# uBus-V1_0.net
KiCad netlist of a schematic drawn in EAGLE
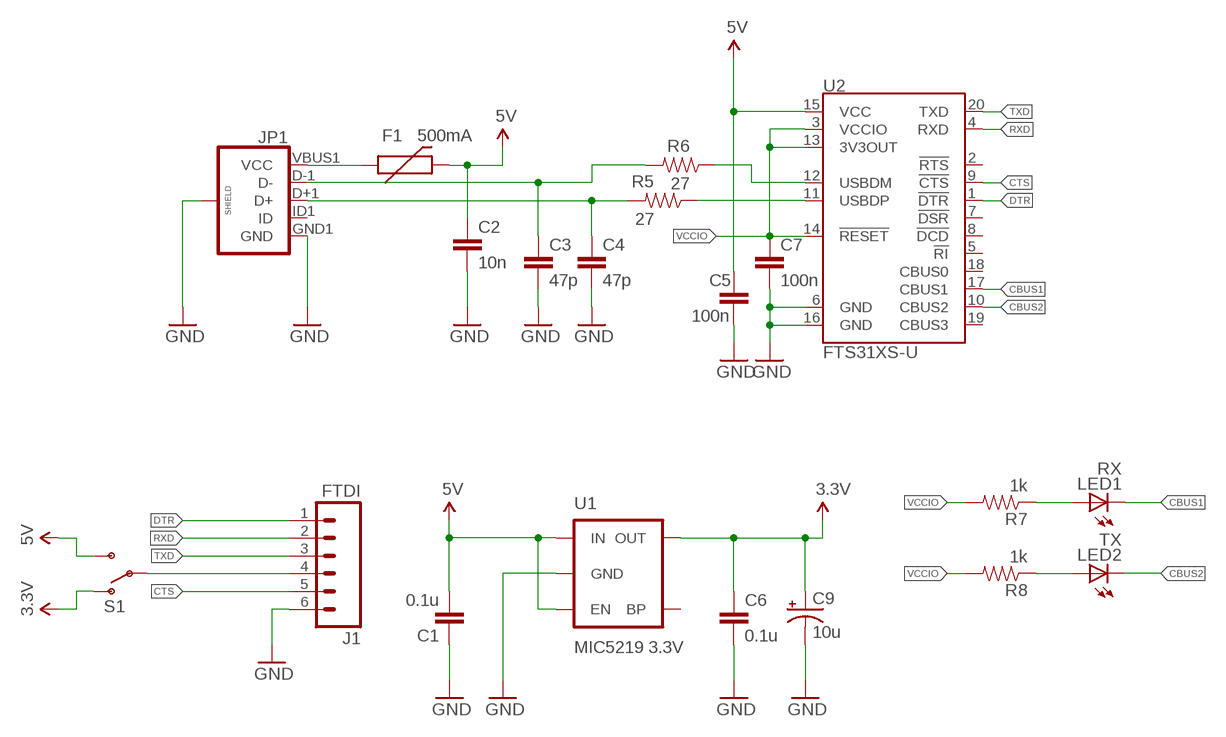
[diagram p0: schematic, sheet 1]

(export (version "E")
  (design (tool "Eeschema 10.0.6"))
  (components
    (comp (ref "C1")
      (value "0.1u")
      (footprint "eagle-import:0603-CAP")
      (libsource (lib "eagle-import") (part "CAP0603-CAP"))
    )
    (comp (ref "C2")
      (value "10n")
      (footprint "eagle-import:0603-CAP")
      (libsource (lib "eagle-import") (part "CAP0603-CAP"))
    )
    (comp (ref "C3")
      (value "47p")
      (footprint "eagle-import:0603-CAP")
      (libsource (lib "eagle-import") (part "CAP0603-CAP"))
    )
    (comp (ref "C4")
      (value "47p")
      (footprint "eagle-import:0603-CAP")
      (libsource (lib "eagle-import") (part "CAP0603-CAP"))
    )
    (comp (ref "C5")
      (value "100n")
      (footprint "eagle-import:0603-CAP")
      (libsource (lib "eagle-import") (part "CAP0603-CAP"))
    )
    (comp (ref "C6")
      (value "0.1u")
      (footprint "eagle-import:0603-CAP")
      (libsource (lib "eagle-import") (part "CAP0603-CAP"))
    )
    (comp (ref "C7")
      (value "100n")
      (footprint "eagle-import:0603-CAP")
      (libsource (lib "eagle-import") (part "CAP0603-CAP"))
    )
    (comp (ref "C9")
      (value "10u")
      (footprint "eagle-import:SMC_P")
      (libsource (lib "eagle-import") (part "CPOL-USSMCP"))
    )
    (comp (ref "F1")
      (value "500mA")
      (footprint "eagle-import:PTC-1206")
      (libsource (lib "eagle-import") (part "PTCSMD"))
    )
    (comp (ref "J1")
      (value "FTDI")
      (footprint "eagle-import:1X06_LONGPADS")
      (libsource (lib "eagle-import") (part "M06LONGPADS"))
    )
    (comp (ref "JP1")
      (value "USB_MICROB_PLUGCONN-11752")
      (footprint "eagle-import:USB-B-MICRO-SMD_V03")
      (libsource (lib "eagle-import") (part "USB_MICROB_PLUGCONN-11752"))
    )
    (comp (ref "LED1")
      (value "RX")
      (footprint "eagle-import:CHIP-LED0603")
      (libsource (lib "eagle-import") (part "LEDCHIP-LED0603"))
    )
    (comp (ref "LED2")
      (value "TX")
      (footprint "eagle-import:CHIP-LED0603")
      (libsource (lib "eagle-import") (part "LEDCHIP-LED0603"))
    )
    (comp (ref "R5")
      (value "27")
      (footprint "eagle-import:0603-RES")
      (libsource (lib "eagle-import") (part "RESISTOR0603-RES"))
    )
    (comp (ref "R6")
      (value "27")
      (footprint "eagle-import:0603-RES")
      (libsource (lib "eagle-import") (part "RESISTOR0603-RES"))
    )
    (comp (ref "R7")
      (value "1k")
      (footprint "eagle-import:0603-RES")
      (libsource (lib "eagle-import") (part "RESISTOR0603-RES"))
    )
    (comp (ref "R8")
      (value "1k")
      (footprint "eagle-import:0603-RES")
      (libsource (lib "eagle-import") (part "RESISTOR0603-RES"))
    )
    (comp (ref "S1")
      (value "SWITCH-SPDT-SMD-A")
      (footprint "eagle-import:SWITCH-SPST-SMD-A")
      (libsource (lib "eagle-import") (part "SWITCH-SPDT-SMD-A"))
    )
    (comp (ref "U1")
      (value "MIC5219 3.3V")
      (footprint "eagle-import:SOT23-5")
      (libsource (lib "eagle-import") (part "V_REG_MIC52193.3V"))
    )
    (comp (ref "U2")
      (value "FTS31XS-U")
      (footprint "eagle-import:SSOP20_L")
      (libsource (lib "eagle-import") (part "FT231XS"))
    )
  )
  (nets
    (net (code "1") (name "3.3V") (class "Default")
      (node (ref "C6") (pin "1") (pinfunction "1_1") (pintype "passive"))
      (node (ref "C9") (pin "+") (pinfunction "+_+") (pintype "passive"))
      (node (ref "S1") (pin "1") (pinfunction "O_1") (pintype "passive"))
      (node (ref "U1") (pin "5") (pinfunction "OUT_5") (pintype "passive"))
    )
    (net (code "2") (name "5V") (class "Default")
      (node (ref "C1") (pin "2") (pinfunction "2_2") (pintype "passive"))
      (node (ref "C2") (pin "1") (pinfunction "1_1") (pintype "passive"))
      (node (ref "C5") (pin "1") (pinfunction "1_1") (pintype "passive"))
      (node (ref "F1") (pin "2") (pinfunction "2_2") (pintype "bidirectional"))
      (node (ref "S1") (pin "3") (pinfunction "S_3") (pintype "passive"))
      (node (ref "U1") (pin "1") (pinfunction "IN_1") (pintype "input"))
      (node (ref "U1") (pin "3") (pinfunction "EN_3") (pintype "input"))
      (node (ref "U2") (pin "15") (pinfunction "VCC_15") (pintype "bidirectional"))
    )
    (net (code "3") (name "CBUS1") (class "Default")
      (node (ref "LED1") (pin "C") (pinfunction "C_C") (pintype "passive"))
      (node (ref "U2") (pin "17") (pinfunction "CBUS1_17") (pintype "bidirectional"))
    )
    (net (code "4") (name "CBUS2") (class "Default")
      (node (ref "LED2") (pin "C") (pinfunction "C_C") (pintype "passive"))
      (node (ref "U2") (pin "10") (pinfunction "CBUS2_10") (pintype "bidirectional"))
    )
    (net (code "5") (name "CTS") (class "Default")
      (node (ref "J1") (pin "5") (pinfunction "5_5") (pintype "passive"))
      (node (ref "U2") (pin "9") (pinfunction "~{CTS}_9") (pintype "bidirectional"))
    )
    (net (code "6") (name "DTR") (class "Default")
      (node (ref "J1") (pin "1") (pinfunction "1_1") (pintype "passive"))
      (node (ref "U2") (pin "1") (pinfunction "~{DTR}_1") (pintype "bidirectional"))
    )
    (net (code "7") (name "GND") (class "Default")
      (node (ref "C1") (pin "1") (pinfunction "1_1") (pintype "passive"))
      (node (ref "C2") (pin "2") (pinfunction "2_2") (pintype "passive"))
      (node (ref "C3") (pin "2") (pinfunction "2_2") (pintype "passive"))
      (node (ref "C4") (pin "2") (pinfunction "2_2") (pintype "passive"))
      (node (ref "C5") (pin "2") (pinfunction "2_2") (pintype "passive"))
      (node (ref "C6") (pin "2") (pinfunction "2_2") (pintype "passive"))
      (node (ref "C7") (pin "2") (pinfunction "2_2") (pintype "passive"))
      (node (ref "C9") (pin "-") (pinfunction "-_-") (pintype "passive"))
      (node (ref "J1") (pin "6") (pinfunction "6_6") (pintype "passive"))
      (node (ref "JP1") (pin "GND1") (pinfunction "GND_GND1") (pintype "bidirectional"))
      (node (ref "JP1") (pin "SHIELD1") (pinfunction "SHIELD_SHIELD1") (pintype "bidirectional"))
      (node (ref "JP1") (pin "SHIELD2") (pinfunction "SHIELD_SHIELD2") (pintype "bidirectional"))
      (node (ref "JP1") (pin "SHIELD3") (pinfunction "SHIELD_SHIELD3") (pintype "bidirectional"))
      (node (ref "U1") (pin "2") (pinfunction "GND_2") (pintype "input"))
      (node (ref "U2") (pin "16") (pinfunction "GND_16") (pintype "bidirectional"))
      (node (ref "U2") (pin "6") (pinfunction "GND_6") (pintype "bidirectional"))
    )
    (net (code "8") (name "Net-(JP1-D+)") (class "Default")
      (node (ref "C4") (pin "1") (pinfunction "1_1") (pintype "passive"))
      (node (ref "JP1") (pin "D+1") (pinfunction "D+_D+1") (pintype "bidirectional"))
      (node (ref "R5") (pin "2") (pinfunction "2_2") (pintype "passive"))
    )
    (net (code "9") (name "Net-(JP1-D-)") (class "Default")
      (node (ref "C3") (pin "1") (pinfunction "1_1") (pintype "passive"))
      (node (ref "JP1") (pin "D-1") (pinfunction "D-_D-1") (pintype "bidirectional"))
      (node (ref "R6") (pin "2") (pinfunction "2_2") (pintype "passive"))
    )
    (net (code "10") (name "Net-(JP1-VCC)") (class "Default")
      (node (ref "F1") (pin "1") (pinfunction "1_1") (pintype "bidirectional"))
      (node (ref "JP1") (pin "VBUS1") (pinfunction "VCC_VBUS1") (pintype "bidirectional"))
    )
    (net (code "11") (name "Net-(LED1-PadA)") (class "Default")
      (node (ref "LED1") (pin "A") (pinfunction "A_A") (pintype "passive"))
      (node (ref "R7") (pin "1") (pinfunction "1_1") (pintype "passive"))
    )
    (net (code "12") (name "Net-(LED2-PadA)") (class "Default")
      (node (ref "LED2") (pin "A") (pinfunction "A_A") (pintype "passive"))
      (node (ref "R8") (pin "1") (pinfunction "1_1") (pintype "passive"))
    )
    (net (code "13") (name "Net-(S1-P)") (class "Default")
      (node (ref "J1") (pin "4") (pinfunction "4_4") (pintype "passive"))
      (node (ref "S1") (pin "2") (pinfunction "P_2") (pintype "passive"))
    )
    (net (code "14") (name "Net-(U2-USBDM)") (class "Default")
      (node (ref "R6") (pin "1") (pinfunction "1_1") (pintype "passive"))
      (node (ref "U2") (pin "12") (pinfunction "USBDM_12") (pintype "bidirectional"))
    )
    (net (code "15") (name "Net-(U2-USBDP)") (class "Default")
      (node (ref "R5") (pin "1") (pinfunction "1_1") (pintype "passive"))
      (node (ref "U2") (pin "11") (pinfunction "USBDP_11") (pintype "bidirectional"))
    )
    (net (code "16") (name "RXD") (class "Default")
      (node (ref "J1") (pin "2") (pinfunction "2_2") (pintype "passive"))
      (node (ref "U2") (pin "4") (pinfunction "RXD_4") (pintype "bidirectional"))
    )
    (net (code "17") (name "TXD") (class "Default")
      (node (ref "J1") (pin "3") (pinfunction "3_3") (pintype "passive"))
      (node (ref "U2") (pin "20") (pinfunction "TXD_20") (pintype "bidirectional"))
    )
    (net (code "18") (name "VCCIO") (class "Default")
      (node (ref "C7") (pin "1") (pinfunction "1_1") (pintype "passive"))
      (node (ref "R7") (pin "2") (pinfunction "2_2") (pintype "passive"))
      (node (ref "R8") (pin "2") (pinfunction "2_2") (pintype "passive"))
      (node (ref "U2") (pin "13") (pinfunction "3V3OUT_13") (pintype "bidirectional"))
      (node (ref "U2") (pin "14") (pinfunction "~{RESET}_14") (pintype "bidirectional"))
      (node (ref "U2") (pin "3") (pinfunction "VCCIO_3") (pintype "bidirectional"))
    )
    (net (code "19") (name "unconnected-(JP1-ID-PadID1)") (class "Default")
      (node (ref "JP1") (pin "ID1") (pinfunction "ID_ID1") (pintype "bidirectional"))
    )
    (net (code "20") (name "unconnected-(U1-BP-Pad4)") (class "Default")
      (node (ref "U1") (pin "4") (pinfunction "BP_4") (pintype "input"))
    )
    (net (code "21") (name "unconnected-(U2-CBUS0-Pad18)") (class "Default")
      (node (ref "U2") (pin "18") (pinfunction "CBUS0_18") (pintype "bidirectional"))
    )
    (net (code "22") (name "unconnected-(U2-CBUS3-Pad19)") (class "Default")
      (node (ref "U2") (pin "19") (pinfunction "CBUS3_19") (pintype "bidirectional"))
    )
    (net (code "23") (name "unconnected-(U2-~{DCD}-Pad8)") (class "Default")
      (node (ref "U2") (pin "8") (pinfunction "~{DCD}_8") (pintype "bidirectional"))
    )
    (net (code "24") (name "unconnected-(U2-~{DSR}-Pad7)") (class "Default")
      (node (ref "U2") (pin "7") (pinfunction "~{DSR}_7") (pintype "bidirectional"))
    )
    (net (code "25") (name "unconnected-(U2-~{RI}-Pad5)") (class "Default")
      (node (ref "U2") (pin "5") (pinfunction "~{RI}_5") (pintype "bidirectional"))
    )
    (net (code "26") (name "unconnected-(U2-~{RTS}-Pad2)") (class "Default")
      (node (ref "U2") (pin "2") (pinfunction "~{RTS}_2") (pintype "bidirectional"))
    )
  )
)
